# CPU2.net
KiCad netlist of a schematic drawn in Altium Designer
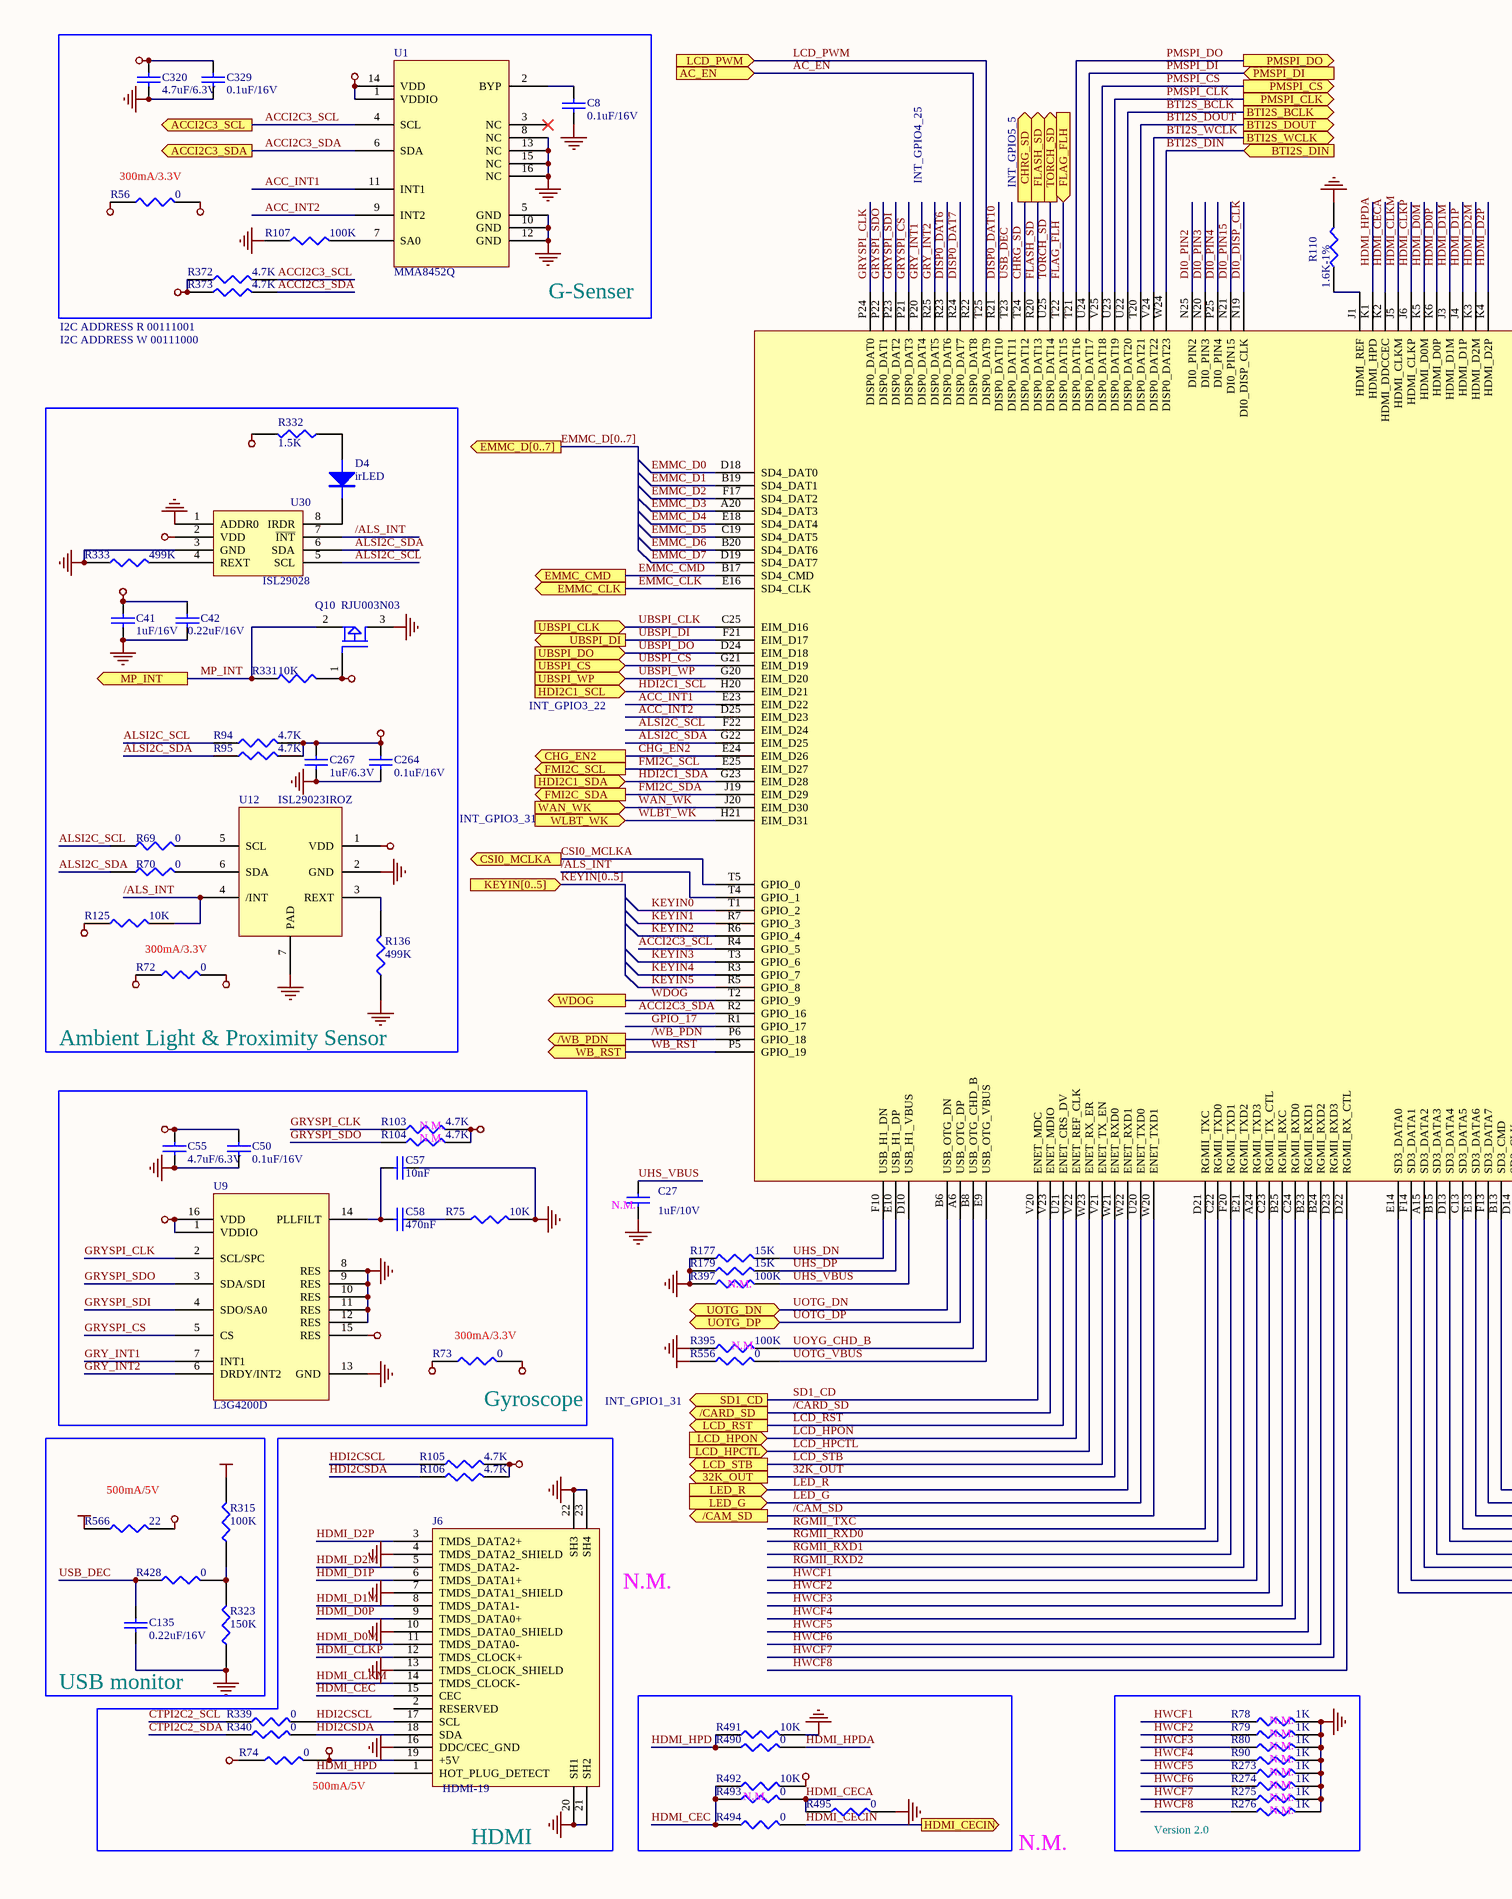
[diagram p0: CPU2.schdoc, left]
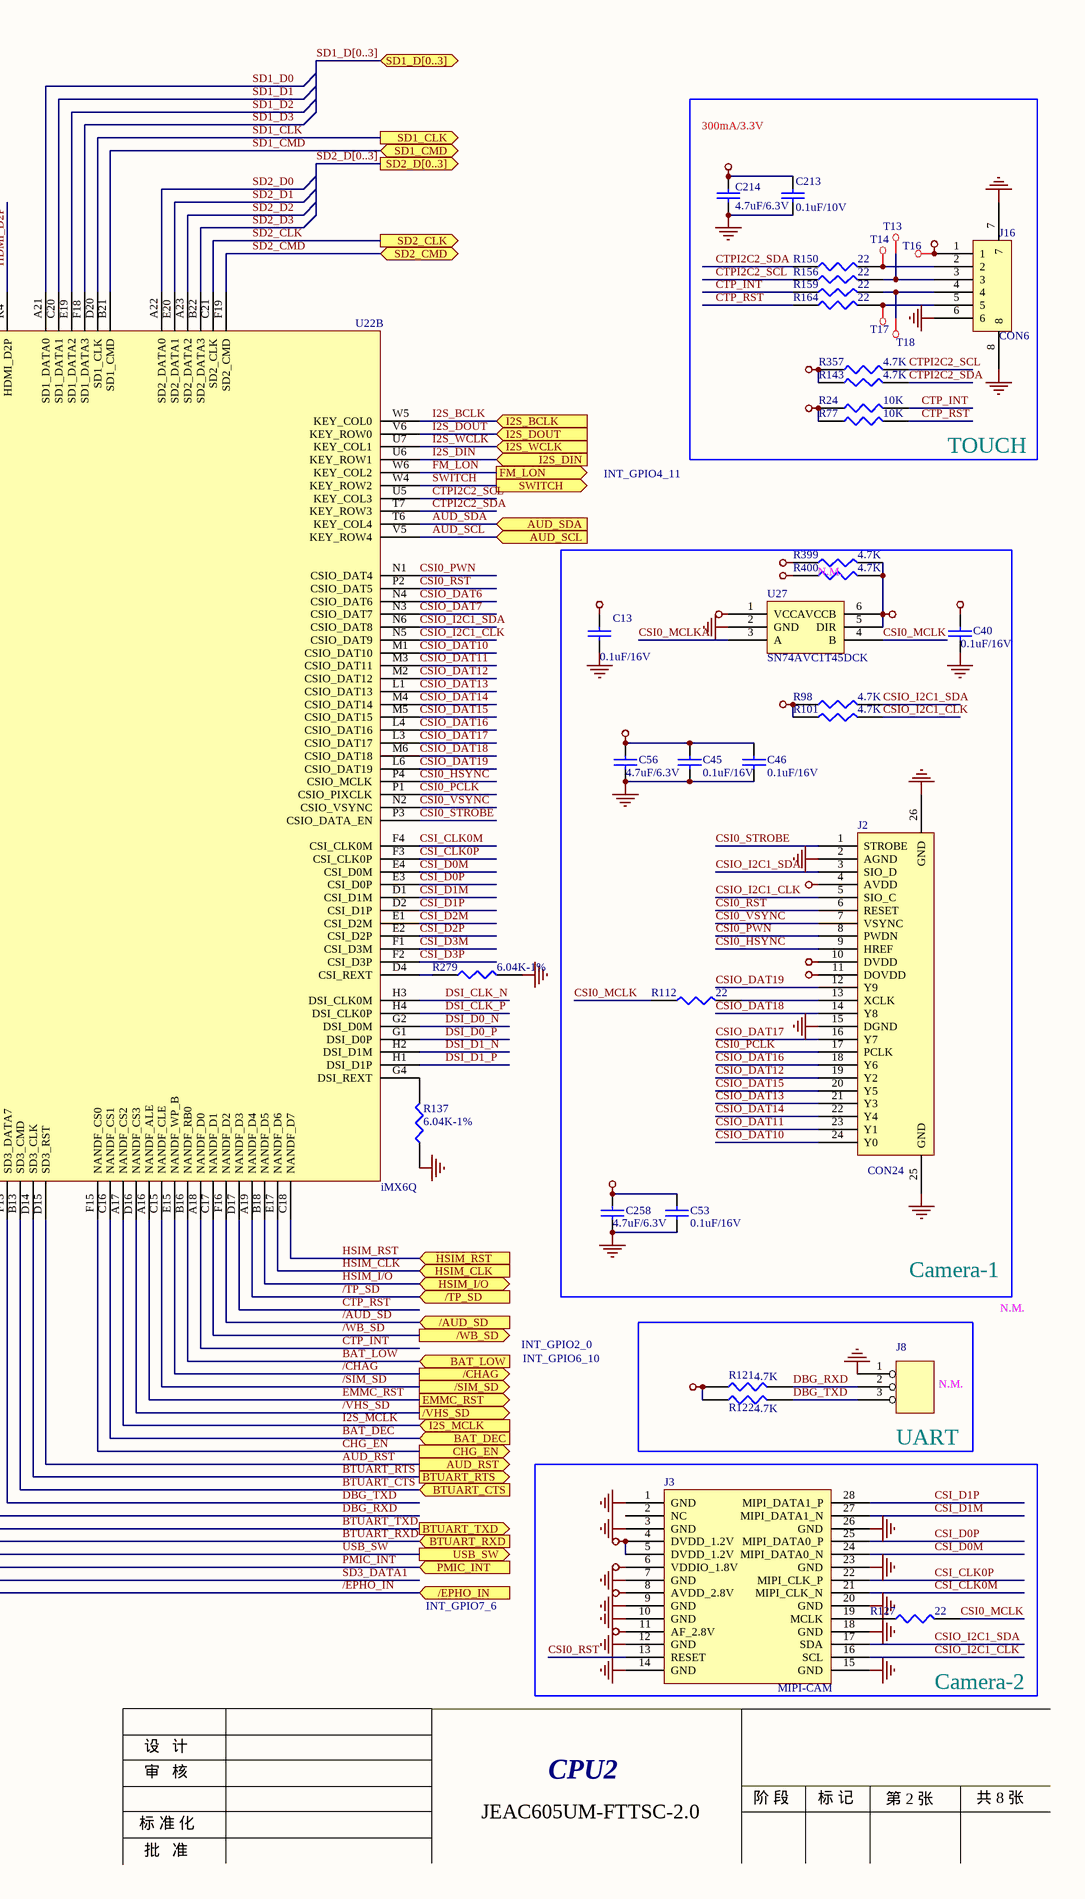
[diagram p1: CPU2.schdoc, right]

(export (version "E")
  (design (tool "Eeschema 10.0.6"))
  (components
    (comp (ref "C8") (value "0.1uF/16V") (footprint "C0402") (libsource (lib "*") (part "CAP")))
    (comp (ref "C13")
      (value "0.1uF/16V")
      (footprint "C0402")
      (description "Capacitor")
      (libsource (lib "*") (part "CAP"))
    )
    (comp (ref "C27")
      (value "1uF/10V")
      (footprint "C0603")
      (description "Capacitor")
      (libsource (lib "*") (part "CAP"))
    )
    (comp (ref "C40")
      (value "0.1uF/16V")
      (footprint "C0402")
      (description "Capacitor")
      (libsource (lib "*") (part "CAP"))
    )
    (comp (ref "C41")
      (value "1uF/16V")
      (footprint "C0402")
      (description "Capacitor")
      (libsource (lib "*") (part "CAP"))
    )
    (comp (ref "C42")
      (value "0.22uF/16V")
      (footprint "C0402")
      (description "Capacitor")
      (libsource (lib "*") (part "CAP"))
    )
    (comp (ref "C45")
      (value "0.1uF/16V")
      (footprint "C0402")
      (description "Capacitor")
      (libsource (lib "*") (part "CAP"))
    )
    (comp (ref "C46")
      (value "0.1uF/16V")
      (footprint "C0402")
      (description "Capacitor")
      (libsource (lib "*") (part "CAP"))
    )
    (comp (ref "C50") (value "0.1uF/16V") (footprint "C0402") (libsource (lib "*") (part "CAP")))
    (comp (ref "C53")
      (value "0.1uF/16V")
      (footprint "C0402")
      (description "Capacitor")
      (libsource (lib "*") (part "CAP"))
    )
    (comp (ref "C55") (value "4.7uF/6.3V") (footprint "C0603") (libsource (lib "*") (part "CAP")))
    (comp (ref "C56")
      (value "4.7uF/6.3V")
      (footprint "C0603")
      (description "Capacitor")
      (libsource (lib "*") (part "CAP"))
    )
    (comp (ref "C57") (value "10nF") (footprint "C0402") (libsource (lib "*") (part "CAP")))
    (comp (ref "C58") (value "470nF") (footprint "C0402") (libsource (lib "*") (part "CAP")))
    (comp (ref "C135")
      (value "0.22uF/16V")
      (footprint "C0402")
      (description "Capacitor")
      (libsource (lib "*") (part "CAP"))
    )
    (comp (ref "C213")
      (value "0.1uF/10V")
      (footprint "C0402")
      (description "Capacitor")
      (libsource (lib "*") (part "CAP"))
    )
    (comp (ref "C214")
      (value "4.7uF/6.3V")
      (footprint "C0603")
      (description "Capacitor")
      (libsource (lib "*") (part "CAP"))
    )
    (comp (ref "C258")
      (value "4.7uF/6.3V")
      (footprint "C0603")
      (description "Capacitor")
      (libsource (lib "*") (part "CAP"))
    )
    (comp (ref "C264") (value "0.1uF/16V") (footprint "C0402") (libsource (lib "*") (part "CAP")))
    (comp (ref "C267") (value "1uF/6.3V") (footprint "C0402") (libsource (lib "*") (part "CAP")))
    (comp (ref "C320") (value "4.7uF/6.3V") (footprint "C0603") (libsource (lib "*") (part "CAP")))
    (comp (ref "C329") (value "0.1uF/16V") (footprint "C0402") (libsource (lib "*") (part "CAP")))
    (comp (ref "D4") (value "irLED") (footprint "R0603") (libsource (lib "*") (part "DIODE")))
    (comp (ref "J2") (value "CON24") (footprint "J-CON-24-0_5") (libsource (lib "*") (part "CON-24")))
    (comp (ref "J3")
      (value "MIPI-CAM")
      (footprint "j-con-GB042-28P-H10-0_4")
      (libsource (lib "*") (part "MIPI-28"))
    )
    (comp (ref "J6") (value "HDMI-19") (footprint "j-con-19-0_4") (libsource (lib "*") (part "HDMI-19")))
    (comp (ref "J8") (value "~") (footprint "J-CON-3-2_1") (libsource (lib "*") (part "3 HEADER")))
    (comp (ref "J16") (value "CON6") (footprint "J-CON-6-0_5-ATOM") (libsource (lib "IMX53") (part "CON6")))
    (comp (ref "Q10") (value "RJU003N03") (footprint "SOT-23") (libsource (lib "*") (part "SI1021")))
    (comp (ref "R24") (value "10K") (footprint "R0402") (libsource (lib "*") (part "RES1")))
    (comp (ref "R56") (value "0") (footprint "R0402") (libsource (lib "*") (part "RES1")))
    (comp (ref "R69") (value "0") (footprint "R0402") (libsource (lib "*") (part "RES1")))
    (comp (ref "R70") (value "0") (footprint "R0402") (libsource (lib "*") (part "RES1")))
    (comp (ref "R72") (value "0") (footprint "R0402") (libsource (lib "*") (part "RES1")))
    (comp (ref "R73") (value "0") (footprint "R0402") (libsource (lib "*") (part "RES1")))
    (comp (ref "R74") (value "0") (footprint "R0603") (libsource (lib "*") (part "RES1")))
    (comp (ref "R75") (value "10K") (footprint "R0402") (libsource (lib "*") (part "RES1")))
    (comp (ref "R77") (value "10K") (footprint "R0402") (libsource (lib "*") (part "RES1")))
    (comp (ref "R78") (value "1K") (footprint "R0402") (libsource (lib "*") (part "RES1")))
    (comp (ref "R79") (value "1K") (footprint "R0402") (libsource (lib "*") (part "RES1")))
    (comp (ref "R80") (value "1K") (footprint "R0402") (libsource (lib "*") (part "RES1")))
    (comp (ref "R90") (value "1K") (footprint "R0402") (libsource (lib "*") (part "RES1")))
    (comp (ref "R94") (value "4.7K") (footprint "R0402") (libsource (lib "*") (part "RES1")))
    (comp (ref "R95") (value "4.7K") (footprint "R0402") (libsource (lib "*") (part "RES1")))
    (comp (ref "R98") (value "4.7K") (footprint "R0402") (libsource (lib "*") (part "RES1")))
    (comp (ref "R101") (value "4.7K") (footprint "R0402") (libsource (lib "*") (part "RES1")))
    (comp (ref "R103") (value "4.7K") (footprint "R0402") (libsource (lib "*") (part "RES1")))
    (comp (ref "R104") (value "4.7K") (footprint "R0402") (libsource (lib "*") (part "RES1")))
    (comp (ref "R105") (value "4.7K") (footprint "R0402") (libsource (lib "*") (part "RES1")))
    (comp (ref "R106") (value "4.7K") (footprint "R0402") (libsource (lib "*") (part "RES1")))
    (comp (ref "R107") (value "100K") (footprint "R0402") (libsource (lib "*") (part "RES1")))
    (comp (ref "R110") (value "1.6K-1%") (footprint "R0402") (libsource (lib "*") (part "RES1")))
    (comp (ref "R112") (value "22") (footprint "R0402") (libsource (lib "*") (part "RES1")))
    (comp (ref "R121") (value "4.7K") (footprint "R0402") (libsource (lib "*") (part "RES1")))
    (comp (ref "R122") (value "4.7K") (footprint "R0402") (libsource (lib "*") (part "RES1")))
    (comp (ref "R125") (value "10K") (footprint "R0402") (libsource (lib "*") (part "RES1")))
    (comp (ref "R127") (value "22") (footprint "R0402") (libsource (lib "*") (part "RES1")))
    (comp (ref "R136") (value "499K") (footprint "R0402") (libsource (lib "*") (part "RES1")))
    (comp (ref "R137") (value "6.04K-1%") (footprint "R0402") (libsource (lib "*") (part "RES1")))
    (comp (ref "R143") (value "4.7K") (footprint "R0402") (libsource (lib "*") (part "RES1")))
    (comp (ref "R150") (value "22") (footprint "R0402") (libsource (lib "*") (part "RES1")))
    (comp (ref "R156") (value "22") (footprint "R0402") (libsource (lib "*") (part "RES1")))
    (comp (ref "R159") (value "22") (footprint "R0402") (libsource (lib "*") (part "RES1")))
    (comp (ref "R164") (value "22") (footprint "R0402") (libsource (lib "*") (part "RES1")))
    (comp (ref "R177") (value "15K") (footprint "R0402") (libsource (lib "*") (part "RES1")))
    (comp (ref "R179") (value "15K") (footprint "R0402") (libsource (lib "*") (part "RES1")))
    (comp (ref "R273") (value "1K") (footprint "R0402") (libsource (lib "*") (part "RES1")))
    (comp (ref "R274") (value "1K") (footprint "R0402") (libsource (lib "*") (part "RES1")))
    (comp (ref "R275") (value "1K") (footprint "R0402") (libsource (lib "*") (part "RES1")))
    (comp (ref "R276") (value "1K") (footprint "R0402") (libsource (lib "*") (part "RES1")))
    (comp (ref "R279") (value "6.04K-1%") (footprint "R0402") (libsource (lib "*") (part "RES1")))
    (comp (ref "R315") (value "100K") (footprint "R0402") (libsource (lib "*") (part "RES1")))
    (comp (ref "R323") (value "150K") (footprint "R0402") (libsource (lib "*") (part "RES1")))
    (comp (ref "R331") (value "10K") (footprint "R0402") (libsource (lib "*") (part "RES1")))
    (comp (ref "R332") (value "1.5K") (footprint "R0402") (libsource (lib "*") (part "RES1")))
    (comp (ref "R333") (value "499K") (footprint "R0402") (libsource (lib "*") (part "RES1")))
    (comp (ref "R339") (value "0") (footprint "R0402") (libsource (lib "*") (part "RES1")))
    (comp (ref "R340") (value "0") (footprint "R0402") (libsource (lib "*") (part "RES1")))
    (comp (ref "R357") (value "4.7K") (footprint "R0402") (libsource (lib "*") (part "RES1")))
    (comp (ref "R372") (value "4.7K") (footprint "R0402") (libsource (lib "*") (part "RES1")))
    (comp (ref "R373") (value "4.7K") (footprint "R0402") (libsource (lib "*") (part "RES1")))
    (comp (ref "R395") (value "100K") (footprint "R0402") (libsource (lib "*") (part "RES1")))
    (comp (ref "R397") (value "100K") (footprint "R0402") (libsource (lib "*") (part "RES1")))
    (comp (ref "R399") (value "4.7K") (footprint "R0402") (libsource (lib "*") (part "RES1")))
    (comp (ref "R400") (value "4.7K") (footprint "R0402") (libsource (lib "*") (part "RES1")))
    (comp (ref "R428") (value "0") (footprint "R0402") (libsource (lib "*") (part "RES1")))
    (comp (ref "R490") (value "0") (footprint "R0402") (libsource (lib "*") (part "RES1")))
    (comp (ref "R491") (value "10K") (footprint "R0402") (libsource (lib "*") (part "RES1")))
    (comp (ref "R492") (value "10K") (footprint "R0402") (libsource (lib "*") (part "RES1")))
    (comp (ref "R493") (value "0") (footprint "R0402") (libsource (lib "*") (part "RES1")))
    (comp (ref "R494") (value "0") (footprint "R0402") (libsource (lib "*") (part "RES1")))
    (comp (ref "R495") (value "0") (footprint "R0402") (libsource (lib "*") (part "RES1")))
    (comp (ref "R556") (value "0") (footprint "R0402") (libsource (lib "*") (part "RES1")))
    (comp (ref "R566") (value "22") (footprint "R0402") (libsource (lib "*") (part "RES1")))
    (comp (ref "T13")
      (value "Testpoint")
      (footprint "TP2_0")
      (libsource (lib "DXP-SCHLIB") (part "Testpoint"))
    )
    (comp (ref "T14")
      (value "Testpoint")
      (footprint "TP2_0")
      (libsource (lib "DXP-SCHLIB") (part "Testpoint"))
    )
    (comp (ref "T16")
      (value "Testpoint")
      (footprint "TP2_0")
      (libsource (lib "DXP-SCHLIB") (part "Testpoint"))
    )
    (comp (ref "T17")
      (value "Testpoint")
      (footprint "TP2_0")
      (libsource (lib "DXP-SCHLIB") (part "Testpoint"))
    )
    (comp (ref "T18")
      (value "Testpoint")
      (footprint "TP2_0")
      (libsource (lib "DXP-SCHLIB") (part "Testpoint"))
    )
    (comp (ref "U1")
      (value "MMA8452Q")
      (footprint "U-DFN-16-0_5")
      (libsource (lib "IMX53") (part "MMA8452Q"))
    )
    (comp (ref "U9")
      (value "L3G4200D")
      (footprint "U-LGA-16-0_65")
      (libsource (lib "IMX53") (part "L3G4200D"))
    )
    (comp (ref "U12")
      (value "ISL29023IROZ")
      (footprint "U-ODFN-6-0_65")
      (libsource (lib "IMX53") (part "ISL29023IROZ"))
    )
    (comp (ref "U22") (value "iMX6Q") (footprint "U-BGA-624-0_8") (libsource (lib "Schlib1") (part "IMX6Q")))
    (comp (ref "U27")
      (value "SN74AVC1T45DCK")
      (footprint "SOT-363-6-0_65")
      (libsource (lib "TPS73701-SOT") (part "Component_1"))
    )
    (comp (ref "U30") (value "ISL29028") (footprint "U-ODFN-8-0_5") (libsource (lib "*") (part "ISL29028")))
  )
  (nets
    (net (code "1") (name "/32K_OUT") (class "Default")
      (node (ref "U22") (pin "W21") (pinfunction "ENET_RXD0_W21") (pintype "passive"))
    )
    (net (code "2") (name "/ACCI2C3_SCL") (class "Default")
      (node (ref "R372") (pin "2") (pinfunction "2_2") (pintype "passive"))
      (node (ref "U1") (pin "4") (pinfunction "SCL_4") (pintype "passive"))
      (node (ref "U22") (pin "R4") (pinfunction "GPIO_5_R4") (pintype "passive"))
    )
    (net (code "3") (name "/ACCI2C3_SDA") (class "Default")
      (node (ref "R373") (pin "2") (pinfunction "2_2") (pintype "passive"))
      (node (ref "U1") (pin "6") (pinfunction "SDA_6") (pintype "passive"))
      (node (ref "U22") (pin "R2") (pinfunction "GPIO_16_R2") (pintype "passive"))
    )
    (net (code "4") (name "/ACC_INT1") (class "Default")
      (node (ref "U1") (pin "11") (pinfunction "INT1_11") (pintype "passive"))
      (node (ref "U22") (pin "E23") (pinfunction "EIM_D22_E23") (pintype "passive"))
    )
    (net (code "5") (name "/ACC_INT2") (class "Default")
      (node (ref "U1") (pin "9") (pinfunction "INT2_9") (pintype "passive"))
      (node (ref "U22") (pin "D25") (pinfunction "EIM_D23_D25") (pintype "passive"))
    )
    (net (code "6") (name "/AC_EN") (class "Default")
      (node (ref "U22") (pin "R22") (pinfunction "DISP0_DAT8_R22") (pintype "passive"))
    )
    (net (code "7") (name "/ALSI2C_SCL") (class "Default")
      (node (ref "R69") (pin "1") (pinfunction "1_1") (pintype "passive"))
      (node (ref "R94") (pin "1") (pinfunction "1_1") (pintype "passive"))
      (node (ref "U22") (pin "F22") (pinfunction "EIM_D24_F22") (pintype "passive"))
      (node (ref "U30") (pin "5") (pinfunction "SCL_5") (pintype "passive"))
    )
    (net (code "8") (name "/ALSI2C_SDA") (class "Default")
      (node (ref "R70") (pin "1") (pinfunction "1_1") (pintype "passive"))
      (node (ref "R95") (pin "1") (pinfunction "1_1") (pintype "passive"))
      (node (ref "U22") (pin "G22") (pinfunction "EIM_D25_G22") (pintype "passive"))
      (node (ref "U30") (pin "6") (pinfunction "SDA_6") (pintype "passive"))
    )
    (net (code "9") (name "/AUD_RST") (class "Default")
      (node (ref "U22") (pin "D15") (pinfunction "SD3_RST_D15") (pintype "passive"))
    )
    (net (code "10") (name "/AUD_SCL") (class "Default")
      (node (ref "U22") (pin "V5") (pinfunction "KEY_ROW4_V5") (pintype "passive"))
    )
    (net (code "11") (name "/AUD_SDA") (class "Default")
      (node (ref "U22") (pin "T6") (pinfunction "KEY_COL4_T6") (pintype "passive"))
    )
    (net (code "12") (name "/BAT_DEC") (class "Default")
      (node (ref "U22") (pin "C16") (pinfunction "NANDF_CS1_C16") (pintype "passive"))
    )
    (net (code "13") (name "/BAT_LOW") (class "Default")
      (node (ref "U22") (pin "B16") (pinfunction "NANDF_RB0_B16") (pintype "passive"))
    )
    (net (code "14") (name "/BTI2S_BCLK") (class "Default")
      (node (ref "U22") (pin "U22") (pinfunction "DISP0_DAT20_U22") (pintype "passive"))
    )
    (net (code "15") (name "/BTI2S_DIN") (class "Default")
      (node (ref "U22") (pin "W24") (pinfunction "DISP0_DAT23_W24") (pintype "passive"))
    )
    (net (code "16") (name "/BTI2S_DOUT") (class "Default")
      (node (ref "U22") (pin "T20") (pinfunction "DISP0_DAT21_T20") (pintype "passive"))
    )
    (net (code "17") (name "/BTI2S_WCLK") (class "Default")
      (node (ref "U22") (pin "V24") (pinfunction "DISP0_DAT22_V24") (pintype "passive"))
    )
    (net (code "18") (name "/BTUART_CTS") (class "Default")
      (node (ref "U22") (pin "B13") (pinfunction "SD3_CMD_B13") (pintype "passive"))
    )
    (net (code "19") (name "/BTUART_RTS") (class "Default")
      (node (ref "U22") (pin "D14") (pinfunction "SD3_CLK_D14") (pintype "passive"))
    )
    (net (code "20") (name "/BTUART_RXD") (class "Default")
      (node (ref "U22") (pin "D13") (pinfunction "SD3_DATA4_D13") (pintype "passive"))
    )
    (net (code "21") (name "/BTUART_TXD") (class "Default")
      (node (ref "U22") (pin "C13") (pinfunction "SD3_DATA5_C13") (pintype "passive"))
    )
    (net (code "22") (name "/CHG_EN") (class "Default")
      (node (ref "U22") (pin "F15") (pinfunction "NANDF_CS0_F15") (pintype "passive"))
    )
    (net (code "23") (name "/CHG_EN2") (class "Default")
      (node (ref "U22") (pin "E24") (pinfunction "EIM_D26_E24") (pintype "passive"))
    )
    (net (code "24") (name "/CHRG_SD") (class "Default")
      (node (ref "U22") (pin "T24") (pinfunction "DISP0_DAT12_T24") (pintype "passive"))
    )
    (net (code "25") (name "/CSI0_HSYNC") (class "Default")
      (node (ref "J2") (pin "9") (pinfunction "HREF_9") (pintype "passive"))
      (node (ref "U22") (pin "P4") (pinfunction "CSIO_MCLK_P4") (pintype "passive"))
    )
    (net (code "26") (name "/CSI0_MCLK") (class "Default")
      (node (ref "R112") (pin "1") (pinfunction "1_1") (pintype "passive"))
      (node (ref "R127") (pin "2") (pinfunction "2_2") (pintype "passive"))
      (node (ref "U27") (pin "4") (pinfunction "B_4") (pintype "passive"))
    )
    (net (code "27") (name "/CSI0_MCLKA") (class "Default")
      (node (ref "U22") (pin "T5") (pinfunction "GPIO_0_T5") (pintype "passive"))
      (node (ref "U27") (pin "3") (pinfunction "A_3") (pintype "passive"))
    )
    (net (code "28") (name "/CSI0_PCLK") (class "Default")
      (node (ref "J2") (pin "17") (pinfunction "PCLK_17") (pintype "passive"))
      (node (ref "U22") (pin "P1") (pinfunction "CSIO_PIXCLK_P1") (pintype "passive"))
    )
    (net (code "29") (name "/CSI0_PWN") (class "Default")
      (node (ref "J2") (pin "8") (pinfunction "PWDN_8") (pintype "passive"))
      (node (ref "U22") (pin "N1") (pinfunction "CSIO_DAT4_N1") (pintype "passive"))
    )
    (net (code "30") (name "/CSI0_RST") (class "Default")
      (node (ref "J2") (pin "6") (pinfunction "RESET_6") (pintype "passive"))
      (node (ref "J3") (pin "13") (pinfunction "RESET_13") (pintype "passive"))
      (node (ref "U22") (pin "P2") (pinfunction "CSIO_DAT5_P2") (pintype "passive"))
    )
    (net (code "31") (name "/CSI0_STROBE") (class "Default")
      (node (ref "J2") (pin "1") (pinfunction "STROBE_1") (pintype "passive"))
      (node (ref "U22") (pin "P3") (pinfunction "CSIO_DATA_EN_P3") (pintype "passive"))
    )
    (net (code "32") (name "/CSI0_VSYNC") (class "Default")
      (node (ref "J2") (pin "7") (pinfunction "VSYNC_7") (pintype "passive"))
      (node (ref "U22") (pin "N2") (pinfunction "CSIO_VSYNC_N2") (pintype "passive"))
    )
    (net (code "33") (name "/CSIO_DAT6") (class "Default")
      (node (ref "U22") (pin "N4") (pinfunction "CSIO_DAT6_N4") (pintype "passive"))
    )
    (net (code "34") (name "/CSIO_DAT7") (class "Default")
      (node (ref "U22") (pin "N3") (pinfunction "CSIO_DAT7_N3") (pintype "passive"))
    )
    (net (code "35") (name "/CSIO_DAT10") (class "Default")
      (node (ref "J2") (pin "24") (pinfunction "Y0_24") (pintype "passive"))
      (node (ref "U22") (pin "M1") (pinfunction "CSIO_DAT10_M1") (pintype "passive"))
    )
    (net (code "36") (name "/CSIO_DAT11") (class "Default")
      (node (ref "J2") (pin "23") (pinfunction "Y1_23") (pintype "passive"))
      (node (ref "U22") (pin "M3") (pinfunction "CSIO_DAT11_M3") (pintype "passive"))
    )
    (net (code "37") (name "/CSIO_DAT12") (class "Default")
      (node (ref "J2") (pin "19") (pinfunction "Y2_19") (pintype "passive"))
      (node (ref "U22") (pin "M2") (pinfunction "CSIO_DAT12_M2") (pintype "passive"))
    )
    (net (code "38") (name "/CSIO_DAT13") (class "Default")
      (node (ref "J2") (pin "21") (pinfunction "Y3_21") (pintype "passive"))
      (node (ref "U22") (pin "L1") (pinfunction "CSIO_DAT13_L1") (pintype "passive"))
    )
    (net (code "39") (name "/CSIO_DAT14") (class "Default")
      (node (ref "J2") (pin "22") (pinfunction "Y4_22") (pintype "passive"))
      (node (ref "U22") (pin "M4") (pinfunction "CSIO_DAT14_M4") (pintype "passive"))
    )
    (net (code "40") (name "/CSIO_DAT15") (class "Default")
      (node (ref "J2") (pin "20") (pinfunction "Y5_20") (pintype "passive"))
      (node (ref "U22") (pin "M5") (pinfunction "CSIO_DAT15_M5") (pintype "passive"))
    )
    (net (code "41") (name "/CSIO_DAT16") (class "Default")
      (node (ref "J2") (pin "18") (pinfunction "Y6_18") (pintype "passive"))
      (node (ref "U22") (pin "L4") (pinfunction "CSIO_DAT16_L4") (pintype "passive"))
    )
    (net (code "42") (name "/CSIO_DAT17") (class "Default")
      (node (ref "J2") (pin "16") (pinfunction "Y7_16") (pintype "passive"))
      (node (ref "U22") (pin "L3") (pinfunction "CSIO_DAT17_L3") (pintype "passive"))
    )
    (net (code "43") (name "/CSIO_DAT18") (class "Default")
      (node (ref "J2") (pin "14") (pinfunction "Y8_14") (pintype "passive"))
      (node (ref "U22") (pin "M6") (pinfunction "CSIO_DAT18_M6") (pintype "passive"))
    )
    (net (code "44") (name "/CSIO_DAT19") (class "Default")
      (node (ref "J2") (pin "12") (pinfunction "Y9_12") (pintype "passive"))
      (node (ref "U22") (pin "L6") (pinfunction "CSIO_DAT19_L6") (pintype "passive"))
    )
    (net (code "45") (name "/CSIO_I2C1_CLK") (class "Default")
      (node (ref "J2") (pin "5") (pinfunction "SIO_C_5") (pintype "passive"))
      (node (ref "J3") (pin "16") (pinfunction "SCL_16") (pintype "passive"))
      (node (ref "R101") (pin "2") (pinfunction "2_2") (pintype "passive"))
      (node (ref "U22") (pin "N5") (pinfunction "CSIO_DAT9_N5") (pintype "passive"))
    )
    (net (code "46") (name "/CSIO_I2C1_SDA") (class "Default")
      (node (ref "J2") (pin "3") (pinfunction "SIO_D_3") (pintype "passive"))
      (node (ref "J3") (pin "17") (pinfunction "SDA_17") (pintype "passive"))
      (node (ref "R98") (pin "2") (pinfunction "2_2") (pintype "passive"))
      (node (ref "U22") (pin "N6") (pinfunction "CSIO_DAT8_N6") (pintype "passive"))
    )
    (net (code "47") (name "/CSI_CLK0M") (class "Default")
      (node (ref "J3") (pin "21") (pinfunction "MIPI_CLK_N_21") (pintype "passive"))
      (node (ref "U22") (pin "F4") (pinfunction "CSI_CLK0M_F4") (pintype "passive"))
    )
    (net (code "48") (name "/CSI_CLK0P") (class "Default")
      (node (ref "J3") (pin "22") (pinfunction "MIPI_CLK_P_22") (pintype "passive"))
      (node (ref "U22") (pin "F3") (pinfunction "CSI_CLK0P_F3") (pintype "passive"))
    )
    (net (code "49") (name "/CSI_D0M") (class "Default")
      (node (ref "J3") (pin "24") (pinfunction "MIPI_DATA0_N_24") (pintype "passive"))
      (node (ref "U22") (pin "E4") (pinfunction "CSI_D0M_E4") (pintype "passive"))
    )
    (net (code "50") (name "/CSI_D0P") (class "Default")
      (node (ref "J3") (pin "25") (pinfunction "MIPI_DATA0_P_25") (pintype "passive"))
      (node (ref "U22") (pin "E3") (pinfunction "CSI_D0P_E3") (pintype "passive"))
    )
    (net (code "51") (name "/CSI_D1M") (class "Default")
      (node (ref "J3") (pin "27") (pinfunction "MIPI_DATA1_N_27") (pintype "passive"))
      (node (ref "U22") (pin "D1") (pinfunction "CSI_D1M_D1") (pintype "passive"))
    )
    (net (code "52") (name "/CSI_D1P") (class "Default")
      (node (ref "J3") (pin "28") (pinfunction "MIPI_DATA1_P_28") (pintype "passive"))
      (node (ref "U22") (pin "D2") (pinfunction "CSI_D1P_D2") (pintype "passive"))
    )
    (net (code "53") (name "/CSI_D2M") (class "Default")
      (node (ref "U22") (pin "E1") (pinfunction "CSI_D2M_E1") (pintype "passive"))
    )
    (net (code "54") (name "/CSI_D2P") (class "Default")
      (node (ref "U22") (pin "E2") (pinfunction "CSI_D2P_E2") (pintype "passive"))
    )
    (net (code "55") (name "/CSI_D3M") (class "Default")
      (node (ref "U22") (pin "F1") (pinfunction "CSI_D3M_F1") (pintype "passive"))
    )
    (net (code "56") (name "/CSI_D3P") (class "Default")
      (node (ref "U22") (pin "F2") (pinfunction "CSI_D3P_F2") (pintype "passive"))
    )
    (net (code "57") (name "/CTPI2C2_SCL") (class "Default")
      (node (ref "R156") (pin "1") (pinfunction "1_1") (pintype "passive"))
      (node (ref "R339") (pin "1") (pinfunction "1_1") (pintype "passive"))
      (node (ref "R357") (pin "2") (pinfunction "2_2") (pintype "passive"))
      (node (ref "U22") (pin "U5") (pinfunction "KEY_COL3_U5") (pintype "passive"))
    )
    (net (code "58") (name "/CTPI2C2_SDA") (class "Default")
      (node (ref "R143") (pin "2") (pinfunction "2_2") (pintype "passive"))
      (node (ref "R150") (pin "1") (pinfunction "1_1") (pintype "passive"))
      (node (ref "R340") (pin "1") (pinfunction "1_1") (pintype "passive"))
      (node (ref "U22") (pin "T7") (pinfunction "KEY_ROW3_T7") (pintype "passive"))
    )
    (net (code "59") (name "/CTP_INT") (class "Default")
      (node (ref "R159") (pin "1") (pinfunction "1_1") (pintype "passive"))
      (node (ref "R24") (pin "2") (pinfunction "2_2") (pintype "passive"))
      (node (ref "U22") (pin "A18") (pinfunction "NANDF_D0_A18") (pintype "passive"))
    )
    (net (code "60") (name "/CTP_RST") (class "Default")
      (node (ref "R164") (pin "1") (pinfunction "1_1") (pintype "passive"))
      (node (ref "R77") (pin "2") (pinfunction "2_2") (pintype "passive"))
      (node (ref "U22") (pin "D17") (pinfunction "NANDF_D3_D17") (pintype "passive"))
    )
    (net (code "61") (name "/DBG_RXD") (class "Default")
      (node (ref "J8") (pin "2") (pintype "passive"))
      (node (ref "R121") (pin "2") (pinfunction "2_2") (pintype "passive"))
      (node (ref "U22") (pin "E13") (pinfunction "SD3_DATA6_E13") (pintype "passive"))
    )
    (net (code "62") (name "/DBG_TXD") (class "Default")
      (node (ref "J8") (pin "3") (pintype "passive"))
      (node (ref "R122") (pin "2") (pinfunction "2_2") (pintype "passive"))
      (node (ref "U22") (pin "F13") (pinfunction "SD3_DATA7_F13") (pintype "passive"))
    )
    (net (code "63") (name "/DI0_DISP_CLK") (class "Default")
      (node (ref "U22") (pin "N19") (pinfunction "DI0_DISP_CLK_N19") (pintype "passive"))
    )
    (net (code "64") (name "/DI0_PIN2") (class "Default")
      (node (ref "U22") (pin "N25") (pinfunction "DI0_PIN2_N25") (pintype "passive"))
    )
    (net (code "65") (name "/DI0_PIN3") (class "Default")
      (node (ref "U22") (pin "N20") (pinfunction "DI0_PIN3_N20") (pintype "passive"))
    )
    (net (code "66") (name "/DI0_PIN4") (class "Default")
      (node (ref "U22") (pin "P25") (pinfunction "DI0_PIN4_P25") (pintype "passive"))
    )
    (net (code "67") (name "/DI0_PIN15") (class "Default")
      (node (ref "U22") (pin "N21") (pinfunction "DI0_PIN15_N21") (pintype "passive"))
    )
    (net (code "68") (name "/DISP0_DAT6") (class "Default")
      (node (ref "U22") (pin "R23") (pinfunction "DISP0_DAT6_R23") (pintype "passive"))
    )
    (net (code "69") (name "/DISP0_DAT7") (class "Default")
      (node (ref "U22") (pin "R24") (pinfunction "DISP0_DAT7_R24") (pintype "passive"))
    )
    (net (code "70") (name "/DISP0_DAT10") (class "Default")
      (node (ref "U22") (pin "R21") (pinfunction "DISP0_DAT10_R21") (pintype "passive"))
    )
    (net (code "71") (name "/DSI_CLK_N") (class "Default")
      (node (ref "U22") (pin "H3") (pinfunction "DSI_CLK0M_H3") (pintype "passive"))
    )
    (net (code "72") (name "/DSI_CLK_P") (class "Default")
      (node (ref "U22") (pin "H4") (pinfunction "DSI_CLK0P_H4") (pintype "passive"))
    )
    (net (code "73") (name "/DSI_D0_N") (class "Default")
      (node (ref "U22") (pin "G2") (pinfunction "DSI_D0M_G2") (pintype "passive"))
    )
    (net (code "74") (name "/DSI_D0_P") (class "Default")
      (node (ref "U22") (pin "G1") (pinfunction "DSI_D0P_G1") (pintype "passive"))
    )
    (net (code "75") (name "/DSI_D1_N") (class "Default")
      (node (ref "U22") (pin "H2") (pinfunction "DSI_D1M_H2") (pintype "passive"))
    )
    (net (code "76") (name "/DSI_D1_P") (class "Default")
      (node (ref "U22") (pin "H1") (pinfunction "DSI_D1P_H1") (pintype "passive"))
    )
    (net (code "77") (name "/EMMC_CLK") (class "Default")
      (node (ref "U22") (pin "E16") (pinfunction "SD4_CLK_E16") (pintype "passive"))
    )
    (net (code "78") (name "/EMMC_CMD") (class "Default")
      (node (ref "U22") (pin "B17") (pinfunction "SD4_CMD_B17") (pintype "passive"))
    )
    (net (code "79") (name "/EMMC_D0") (class "Default")
      (node (ref "U22") (pin "D18") (pinfunction "SD4_DAT0_D18") (pintype "passive"))
    )
    (net (code "80") (name "/EMMC_D1") (class "Default")
      (node (ref "U22") (pin "B19") (pinfunction "SD4_DAT1_B19") (pintype "passive"))
    )
    (net (code "81") (name "/EMMC_D2") (class "Default")
      (node (ref "U22") (pin "F17") (pinfunction "SD4_DAT2_F17") (pintype "passive"))
    )
    (net (code "82") (name "/EMMC_D3") (class "Default")
      (node (ref "U22") (pin "A20") (pinfunction "SD4_DAT3_A20") (pintype "passive"))
    )
    (net (code "83") (name "/EMMC_D4") (class "Default")
      (node (ref "U22") (pin "E18") (pinfunction "SD4_DAT4_E18") (pintype "passive"))
    )
    (net (code "84") (name "/EMMC_D5") (class "Default")
      (node (ref "U22") (pin "C19") (pinfunction "SD4_DAT5_C19") (pintype "passive"))
    )
    (net (code "85") (name "/EMMC_D6") (class "Default")
      (node (ref "U22") (pin "B20") (pinfunction "SD4_DAT6_B20") (pintype "passive"))
    )
    (net (code "86") (name "/EMMC_D7") (class "Default")
      (node (ref "U22") (pin "D19") (pinfunction "SD4_DAT7_D19") (pintype "passive"))
    )
    (net (code "88") (name "/EMMC_RST") (class "Default")
      (node (ref "U22") (pin "A16") (pinfunction "NANDF_ALE_A16") (pintype "passive"))
    )
    (net (code "89") (name "/FLAG_FLH") (class "Default")
      (node (ref "U22") (pin "T22") (pinfunction "DISP0_DAT15_T22") (pintype "passive"))
    )
    (net (code "90") (name "/FLASH_SD") (class "Default")
      (node (ref "U22") (pin "R20") (pinfunction "DISP0_DAT13_R20") (pintype "passive"))
    )
    (net (code "91") (name "/FMI2C_SCL") (class "Default")
      (node (ref "U22") (pin "E25") (pinfunction "EIM_D27_E25") (pintype "passive"))
    )
    (net (code "92") (name "/FMI2C_SDA") (class "Default")
      (node (ref "U22") (pin "J19") (pinfunction "EIM_D29_J19") (pintype "passive"))
    )
    (net (code "93") (name "/FM_LON") (class "Default")
      (node (ref "U22") (pin "W6") (pinfunction "KEY_COL2_W6") (pintype "passive"))
    )
    (net (code "94") (name "/GPIO_17") (class "Default")
      (node (ref "U22") (pin "R1") (pinfunction "GPIO_17_R1") (pintype "passive"))
    )
    (net (code "95") (name "/GRYSPI_CLK") (class "Default")
      (node (ref "R103") (pin "1") (pinfunction "1_1") (pintype "passive"))
      (node (ref "U22") (pin "P24") (pinfunction "DISP0_DAT0_P24") (pintype "passive"))
      (node (ref "U9") (pin "2") (pinfunction "SCL/SPC_2") (pintype "passive"))
    )
    (net (code "96") (name "/GRYSPI_CS") (class "Default")
      (node (ref "U22") (pin "P21") (pinfunction "DISP0_DAT3_P21") (pintype "passive"))
      (node (ref "U9") (pin "5") (pinfunction "CS_5") (pintype "passive"))
    )
    (net (code "97") (name "/GRYSPI_SDI") (class "Default")
      (node (ref "U22") (pin "P23") (pinfunction "DISP0_DAT2_P23") (pintype "passive"))
      (node (ref "U9") (pin "4") (pinfunction "SDO/SA0_4") (pintype "passive"))
    )
    (net (code "98") (name "/GRYSPI_SDO") (class "Default")
      (node (ref "R104") (pin "1") (pinfunction "1_1") (pintype "passive"))
      (node (ref "U22") (pin "P22") (pinfunction "DISP0_DAT1_P22") (pintype "passive"))
      (node (ref "U9") (pin "3") (pinfunction "SDA/SDI_3") (pintype "passive"))
    )
    (net (code "99") (name "/GRY_INT1") (class "Default")
      (node (ref "U22") (pin "P20") (pinfunction "DISP0_DAT4_P20") (pintype "passive"))
      (node (ref "U9") (pin "7") (pinfunction "INT1_7") (pintype "passive"))
    )
    (net (code "100") (name "/GRY_INT2") (class "Default")
      (node (ref "U22") (pin "R25") (pinfunction "DISP0_DAT5_R25") (pintype "passive"))
      (node (ref "U9") (pin "6") (pinfunction "DRDY/INT2_6") (pintype "passive"))
    )
    (net (code "101") (name "/HDI2C1_SCL") (class "Default")
      (node (ref "U22") (pin "H20") (pinfunction "EIM_D21_H20") (pintype "passive"))
    )
    (net (code "102") (name "/HDI2C1_SDA") (class "Default")
      (node (ref "U22") (pin "G23") (pinfunction "EIM_D28_G23") (pintype "passive"))
    )
    (net (code "103") (name "/HDI2CSCL") (class "Default")
      (node (ref "J6") (pin "17") (pinfunction "SCL_17") (pintype "passive"))
      (node (ref "R105") (pin "1") (pinfunction "1_1") (pintype "passive"))
      (node (ref "R339") (pin "2") (pinfunction "2_2") (pintype "passive"))
    )
    (net (code "104") (name "/HDI2CSDA") (class "Default")
      (node (ref "J6") (pin "18") (pinfunction "SDA_18") (pintype "passive"))
      (node (ref "R106") (pin "1") (pinfunction "1_1") (pintype "passive"))
      (node (ref "R340") (pin "2") (pinfunction "2_2") (pintype "passive"))
    )
    (net (code "105") (name "/HDMI_CEC") (class "Default")
      (node (ref "J6") (pin "15") (pinfunction "CEC_15") (pintype "passive"))
      (node (ref "R492") (pin "1") (pinfunction "1_1") (pintype "passive"))
      (node (ref "R493") (pin "1") (pinfunction "1_1") (pintype "passive"))
      (node (ref "R494") (pin "1") (pinfunction "1_1") (pintype "passive"))
    )
    (net (code "106") (name "/HDMI_CECA") (class "Default")
      (node (ref "R493") (pin "2") (pinfunction "2_2") (pintype "passive"))
      (node (ref "R495") (pin "1") (pinfunction "1_1") (pintype "passive"))
      (node (ref "U22") (pin "K2") (pinfunction "HDMI_DDCCEC_K2") (pintype "passive"))
    )
    (net (code "107") (name "/HDMI_CECIN") (class "Default")
      (node (ref "R494") (pin "2") (pinfunction "2_2") (pintype "passive"))
    )
    (net (code "108") (name "/HDMI_CLKM") (class "Default")
      (node (ref "J6") (pin "14") (pinfunction "TMDS_CLOCK-_14") (pintype "passive"))
      (node (ref "U22") (pin "J5") (pinfunction "HDMI_CLKM_J5") (pintype "passive"))
    )
    (net (code "109") (name "/HDMI_CLKP") (class "Default")
      (node (ref "J6") (pin "12") (pinfunction "TMDS_CLOCK+_12") (pintype "passive"))
      (node (ref "U22") (pin "J6") (pinfunction "HDMI_CLKP_J6") (pintype "passive"))
    )
    (net (code "110") (name "/HDMI_D0M") (class "Default")
      (node (ref "J6") (pin "11") (pinfunction "TMDS_DATA0-_11") (pintype "passive"))
      (node (ref "U22") (pin "K5") (pinfunction "HDMI_D0M_K5") (pintype "passive"))
    )
    (net (code "111") (name "/HDMI_D0P") (class "Default")
      (node (ref "J6") (pin "9") (pinfunction "TMDS_DATA0+_9") (pintype "passive"))
      (node (ref "U22") (pin "K6") (pinfunction "HDMI_D0P_K6") (pintype "passive"))
    )
    (net (code "112") (name "/HDMI_D1M") (class "Default")
      (node (ref "J6") (pin "8") (pinfunction "TMDS_DATA1-_8") (pintype "passive"))
      (node (ref "U22") (pin "J3") (pinfunction "HDMI_D1M_J3") (pintype "passive"))
    )
    (net (code "113") (name "/HDMI_D1P") (class "Default")
      (node (ref "J6") (pin "6") (pinfunction "TMDS_DATA1+_6") (pintype "passive"))
      (node (ref "U22") (pin "J4") (pinfunction "HDMI_D1P_J4") (pintype "passive"))
    )
    (net (code "114") (name "/HDMI_D2M") (class "Default")
      (node (ref "J6") (pin "5") (pinfunction "TMDS_DATA2-_5") (pintype "passive"))
      (node (ref "U22") (pin "K3") (pinfunction "HDMI_D2M_K3") (pintype "passive"))
    )
    (net (code "115") (name "/HDMI_D2P") (class "Default")
      (node (ref "J6") (pin "3") (pinfunction "TMDS_DATA2+_3") (pintype "passive"))
      (node (ref "U22") (pin "K4") (pinfunction "HDMI_D2P_K4") (pintype "passive"))
    )
    (net (code "116") (name "/HDMI_HPD") (class "Default")
      (node (ref "J6") (pin "1") (pinfunction "HOT_PLUG_DETECT_1") (pintype "passive"))
      (node (ref "R490") (pin "1") (pinfunction "1_1") (pintype "passive"))
      (node (ref "R491") (pin "1") (pinfunction "1_1") (pintype "passive"))
    )
    (net (code "117") (name "/HDMI_HPDA") (class "Default")
      (node (ref "R490") (pin "2") (pinfunction "2_2") (pintype "passive"))
      (node (ref "U22") (pin "K1") (pinfunction "HDMI_HPD_K1") (pintype "passive"))
    )
    (net (code "118") (name "/HSIM_CLK") (class "Default")
      (node (ref "U22") (pin "E17") (pinfunction "NANDF_D6_E17") (pintype "passive"))
    )
    (net (code "119") (name "/HSIM_I{slash}O") (class "Default")
      (node (ref "U22") (pin "B18") (pinfunction "NANDF_D5_B18") (pintype "passive"))
    )
    (net (code "120") (name "/HSIM_RST") (class "Default")
      (node (ref "U22") (pin "C18") (pinfunction "NANDF_D7_C18") (pintype "passive"))
    )
    (net (code "121") (name "/HWCF1") (class "Default")
      (node (ref "R78") (pin "1") (pinfunction "1_1") (pintype "passive"))
      (node (ref "U22") (pin "A24") (pinfunction "RGMII_TXD3_A24") (pintype "passive"))
    )
    (net (code "122") (name "/HWCF2") (class "Default")
      (node (ref "R79") (pin "1") (pinfunction "1_1") (pintype "passive"))
      (node (ref "U22") (pin "C23") (pinfunction "RGMII_TX_CTL_C23") (pintype "passive"))
    )
    (net (code "123") (name "/HWCF3") (class "Default")
      (node (ref "R80") (pin "1") (pinfunction "1_1") (pintype "passive"))
      (node (ref "U22") (pin "B25") (pinfunction "RGMII_RXC_B25") (pintype "passive"))
    )
    (net (code "124") (name "/HWCF4") (class "Default")
      (node (ref "R90") (pin "1") (pinfunction "1_1") (pintype "passive"))
      (node (ref "U22") (pin "C24") (pinfunction "RGMII_RXD0_C24") (pintype "passive"))
    )
    (net (code "125") (name "/HWCF5") (class "Default")
      (node (ref "R273") (pin "1") (pinfunction "1_1") (pintype "passive"))
      (node (ref "U22") (pin "B23") (pinfunction "RGMII_RXD1_B23") (pintype "passive"))
    )
    (net (code "126") (name "/HWCF6") (class "Default")
      (node (ref "R274") (pin "1") (pinfunction "1_1") (pintype "passive"))
      (node (ref "U22") (pin "B24") (pinfunction "RGMII_RXD2_B24") (pintype "passive"))
    )
    (net (code "127") (name "/HWCF7") (class "Default")
      (node (ref "R275") (pin "1") (pinfunction "1_1") (pintype "passive"))
      (node (ref "U22") (pin "D23") (pinfunction "RGMII_RXD3_D23") (pintype "passive"))
    )
    (net (code "128") (name "/HWCF8") (class "Default")
      (node (ref "R276") (pin "1") (pinfunction "1_1") (pintype "passive"))
      (node (ref "U22") (pin "D22") (pinfunction "RGMII_RX_CTL_D22") (pintype "passive"))
    )
    (net (code "129") (name "/I2S_BCLK") (class "Default")
      (node (ref "U22") (pin "W5") (pinfunction "KEY_COL0_W5") (pintype "passive"))
    )
    (net (code "130") (name "/I2S_DIN") (class "Default")
      (node (ref "U22") (pin "U6") (pinfunction "KEY_ROW1_U6") (pintype "passive"))
    )
    (net (code "131") (name "/I2S_DOUT") (class "Default")
      (node (ref "U22") (pin "V6") (pinfunction "KEY_ROW0_V6") (pintype "passive"))
    )
    (net (code "132") (name "/I2S_MCLK") (class "Default")
      (node (ref "U22") (pin "A17") (pinfunction "NANDF_CS2_A17") (pintype "passive"))
    )
    (net (code "133") (name "/I2S_WCLK") (class "Default")
      (node (ref "U22") (pin "U7") (pinfunction "KEY_COL1_U7") (pintype "passive"))
    )
    (net (code "134") (name "/KEYIN0") (class "Default")
      (node (ref "U22") (pin "T1") (pinfunction "GPIO_2_T1") (pintype "passive"))
    )
    (net (code "135") (name "/KEYIN1") (class "Default")
      (node (ref "U22") (pin "R7") (pinfunction "GPIO_3_R7") (pintype "passive"))
    )
    (net (code "136") (name "/KEYIN2") (class "Default")
      (node (ref "U22") (pin "R6") (pinfunction "GPIO_4_R6") (pintype "passive"))
    )
    (net (code "137") (name "/KEYIN3") (class "Default")
      (node (ref "U22") (pin "T3") (pinfunction "GPIO_6_T3") (pintype "passive"))
    )
    (net (code "138") (name "/KEYIN4") (class "Default")
      (node (ref "U22") (pin "R3") (pinfunction "GPIO_7_R3") (pintype "passive"))
    )
    (net (code "139") (name "/KEYIN5") (class "Default")
      (node (ref "U22") (pin "R5") (pinfunction "GPIO_8_R5") (pintype "passive"))
    )
    (net (code "141") (name "/LCD_HPCTL") (class "Default")
      (node (ref "U22") (pin "W23") (pinfunction "ENET_RX_ER_W23") (pintype "passive"))
    )
    (net (code "142") (name "/LCD_HPON") (class "Default")
      (node (ref "U22") (pin "V22") (pinfunction "ENET_REF_CLK_V22") (pintype "passive"))
    )
    (net (code "143") (name "/LCD_PWM") (class "Default")
      (node (ref "U22") (pin "T25") (pinfunction "DISP0_DAT9_T25") (pintype "passive"))
    )
    (net (code "144") (name "/LCD_RST") (class "Default")
      (node (ref "U22") (pin "U21") (pinfunction "ENET_CRS_DV_U21") (pintype "passive"))
    )
    (net (code "145") (name "/LCD_STB") (class "Default")
      (node (ref "U22") (pin "V21") (pinfunction "ENET_TX_EN_V21") (pintype "passive"))
    )
    (net (code "146") (name "/LED_G") (class "Default")
      (node (ref "U22") (pin "U20") (pinfunction "ENET_TXD0_U20") (pintype "passive"))
    )
    (net (code "147") (name "/LED_R") (class "Default")
      (node (ref "U22") (pin "W22") (pinfunction "ENET_RXD1_W22") (pintype "passive"))
    )
    (net (code "148") (name "/MP_INT") (class "Default")
      (node (ref "Q10") (pin "2") (pinfunction "S_2") (pintype "passive"))
      (node (ref "R331") (pin "1") (pinfunction "1_1") (pintype "passive"))
    )
    (net (code "149") (name "/PMIC_INT") (class "Default")
      (node (ref "U22") (pin "A15") (pinfunction "SD3_DATA2_A15") (pintype "passive"))
    )
    (net (code "150") (name "/PMSPI_CLK") (class "Default")
      (node (ref "U22") (pin "U23") (pinfunction "DISP0_DAT19_U23") (pintype "passive"))
    )
    (net (code "151") (name "/PMSPI_CS") (class "Default")
      (node (ref "U22") (pin "V25") (pinfunction "DISP0_DAT18_V25") (pintype "passive"))
    )
    (net (code "152") (name "/PMSPI_DI") (class "Default")
      (node (ref "U22") (pin "U24") (pinfunction "DISP0_DAT17_U24") (pintype "passive"))
    )
    (net (code "153") (name "/PMSPI_DO") (class "Default")
      (node (ref "U22") (pin "T21") (pinfunction "DISP0_DAT16_T21") (pintype "passive"))
    )
    (net (code "154") (name "/RGMII_RXD0") (class "Default")
      (node (ref "U22") (pin "C22") (pinfunction "RGMII_TXD0_C22") (pintype "passive"))
    )
    (net (code "155") (name "/RGMII_RXD1") (class "Default")
      (node (ref "U22") (pin "F20") (pinfunction "RGMII_TXD1_F20") (pintype "passive"))
    )
    (net (code "156") (name "/RGMII_RXD2") (class "Default")
      (node (ref "U22") (pin "E21") (pinfunction "RGMII_TXD2_E21") (pintype "passive"))
    )
    (net (code "157") (name "/RGMII_TXC") (class "Default")
      (node (ref "U22") (pin "D21") (pinfunction "RGMII_TXC_D21") (pintype "passive"))
    )
    (net (code "158") (name "/SD1_CD") (class "Default")
      (node (ref "U22") (pin "V20") (pinfunction "ENET_MDC_V20") (pintype "passive"))
    )
    (net (code "159") (name "/SD1_CLK") (class "Default")
      (node (ref "U22") (pin "D20") (pinfunction "SD1_CLK_D20") (pintype "passive"))
    )
    (net (code "160") (name "/SD1_CMD") (class "Default")
      (node (ref "U22") (pin "B21") (pinfunction "SD1_CMD_B21") (pintype "passive"))
    )
    (net (code "161") (name "/SD1_D0") (class "Default")
      (node (ref "U22") (pin "A21") (pinfunction "SD1_DATA0_A21") (pintype "passive"))
    )
    (net (code "162") (name "/SD1_D1") (class "Default")
      (node (ref "U22") (pin "C20") (pinfunction "SD1_DATA1_C20") (pintype "passive"))
    )
    (net (code "163") (name "/SD1_D2") (class "Default")
      (node (ref "U22") (pin "E19") (pinfunction "SD1_DATA2_E19") (pintype "passive"))
    )
    (net (code "164") (name "/SD1_D3") (class "Default")
      (node (ref "U22") (pin "F18") (pinfunction "SD1_DATA3_F18") (pintype "passive"))
    )
    (net (code "166") (name "/SD2_CLK") (class "Default")
      (node (ref "U22") (pin "C21") (pinfunction "SD2_CLK_C21") (pintype "passive"))
    )
    (net (code "167") (name "/SD2_CMD") (class "Default")
      (node (ref "U22") (pin "F19") (pinfunction "SD2_CMD_F19") (pintype "passive"))
    )
    (net (code "168") (name "/SD2_D0") (class "Default")
      (node (ref "U22") (pin "A22") (pinfunction "SD2_DATA0_A22") (pintype "passive"))
    )
    (net (code "169") (name "/SD2_D1") (class "Default")
      (node (ref "U22") (pin "E20") (pinfunction "SD2_DATA1_E20") (pintype "passive"))
    )
    (net (code "170") (name "/SD2_D2") (class "Default")
      (node (ref "U22") (pin "A23") (pinfunction "SD2_DATA2_A23") (pintype "passive"))
    )
    (net (code "171") (name "/SD2_D3") (class "Default")
      (node (ref "U22") (pin "B22") (pinfunction "SD2_DATA3_B22") (pintype "passive"))
    )
    (net (code "173") (name "/SD3_DATA1") (class "Default")
      (node (ref "U22") (pin "F14") (pinfunction "SD3_DATA1_F14") (pintype "passive"))
    )
    (net (code "174") (name "/SWITCH") (class "Default")
      (node (ref "U22") (pin "W4") (pinfunction "KEY_ROW2_W4") (pintype "passive"))
    )
    (net (code "175") (name "/TORCH_SD") (class "Default")
      (node (ref "U22") (pin "U25") (pinfunction "DISP0_DAT14_U25") (pintype "passive"))
    )
    (net (code "176") (name "/UBSPI_CLK") (class "Default")
      (node (ref "U22") (pin "C25") (pinfunction "EIM_D16_C25") (pintype "passive"))
    )
    (net (code "177") (name "/UBSPI_CS") (class "Default")
      (node (ref "U22") (pin "G21") (pinfunction "EIM_D19_G21") (pintype "passive"))
    )
    (net (code "178") (name "/UBSPI_DI") (class "Default")
      (node (ref "U22") (pin "F21") (pinfunction "EIM_D17_F21") (pintype "passive"))
    )
    (net (code "179") (name "/UBSPI_DO") (class "Default")
      (node (ref "U22") (pin "D24") (pinfunction "EIM_D18_D24") (pintype "passive"))
    )
    (net (code "180") (name "/UBSPI_WP") (class "Default")
      (node (ref "U22") (pin "G20") (pinfunction "EIM_D20_G20") (pintype "passive"))
    )
    (net (code "181") (name "/UHS_DN") (class "Default")
      (node (ref "R177") (pin "2") (pinfunction "2_2") (pintype "passive"))
      (node (ref "U22") (pin "F10") (pinfunction "USB_H1_DN_F10") (pintype "passive"))
    )
    (net (code "182") (name "/UHS_DP") (class "Default")
      (node (ref "R179") (pin "2") (pinfunction "2_2") (pintype "passive"))
      (node (ref "U22") (pin "E10") (pinfunction "USB_H1_DP_E10") (pintype "passive"))
    )
    (net (code "183") (name "/UHS_VBUS") (class "Default")
      (node (ref "C27") (pin "1") (pinfunction "1_1") (pintype "passive"))
      (node (ref "R397") (pin "2") (pinfunction "2_2") (pintype "passive"))
      (node (ref "U22") (pin "D10") (pinfunction "USB_H1_VBUS_D10") (pintype "passive"))
    )
    (net (code "184") (name "/UOTG_DN") (class "Default")
      (node (ref "U22") (pin "B6") (pinfunction "USB_OTG_DN_B6") (pintype "passive"))
    )
    (net (code "185") (name "/UOTG_DP") (class "Default")
      (node (ref "U22") (pin "A6") (pinfunction "USB_OTG_DP_A6") (pintype "passive"))
    )
    (net (code "186") (name "/UOTG_VBUS") (class "Default")
      (node (ref "R556") (pin "2") (pinfunction "2_2") (pintype "passive"))
      (node (ref "U22") (pin "E9") (pinfunction "USB_OTG_VBUS_E9") (pintype "passive"))
    )
    (net (code "187") (name "/UOYG_CHD_B") (class "Default")
      (node (ref "R395") (pin "2") (pinfunction "2_2") (pintype "passive"))
      (node (ref "U22") (pin "B8") (pinfunction "USB_OTG_CHD_B_B8") (pintype "passive"))
    )
    (net (code "188") (name "/USB_DEC") (class "Default")
      (node (ref "C135") (pin "1") (pinfunction "1_1") (pintype "passive"))
      (node (ref "R428") (pin "1") (pinfunction "1_1") (pintype "passive"))
      (node (ref "U22") (pin "T23") (pinfunction "DISP0_DAT11_T23") (pintype "passive"))
    )
    (net (code "189") (name "/USB_SW") (class "Default")
      (node (ref "U22") (pin "B15") (pinfunction "SD3_DATA3_B15") (pintype "passive"))
    )
    (net (code "190") (name "/WAN_WK") (class "Default")
      (node (ref "U22") (pin "J20") (pinfunction "EIM_D30_J20") (pintype "passive"))
    )
    (net (code "191") (name "/WB_RST") (class "Default")
      (node (ref "U22") (pin "P5") (pinfunction "GPIO_19_P5") (pintype "passive"))
    )
    (net (code "192") (name "/WDOG") (class "Default")
      (node (ref "U22") (pin "T2") (pinfunction "GPIO_9_T2") (pintype "passive"))
    )
    (net (code "193") (name "/WLBT_WK") (class "Default")
      (node (ref "U22") (pin "H21") (pinfunction "EIM_D31_H21") (pintype "passive"))
    )
    (net (code "194") (name "/{slash}ALS_INT") (class "Default")
      (node (ref "R125") (pin "2") (pinfunction "2_2") (pintype "passive"))
      (node (ref "U12") (pin "4") (pinfunction "/INT_4") (pintype "passive"))
      (node (ref "U22") (pin "T4") (pinfunction "GPIO_1_T4") (pintype "passive"))
      (node (ref "U30") (pin "7") (pinfunction "~{INT}_7") (pintype "passive"))
    )
    (net (code "195") (name "/{slash}AUD_SD") (class "Default")
      (node (ref "U22") (pin "F16") (pinfunction "NANDF_D2_F16") (pintype "passive"))
    )
    (net (code "196") (name "/{slash}CAM_SD") (class "Default")
      (node (ref "U22") (pin "W20") (pinfunction "ENET_TXD1_W20") (pintype "passive"))
    )
    (net (code "197") (name "/{slash}CARD_SD") (class "Default")
      (node (ref "U22") (pin "V23") (pinfunction "ENET_MDIO_V23") (pintype "passive"))
    )
    (net (code "198") (name "/{slash}CHAG") (class "Default")
      (node (ref "U22") (pin "E15") (pinfunction "NANDF_WP_B_E15") (pintype "passive"))
    )
    (net (code "199") (name "/{slash}EPHO_IN") (class "Default")
      (node (ref "U22") (pin "E14") (pinfunction "SD3_DATA0_E14") (pintype "passive"))
    )
    (net (code "200") (name "/{slash}SIM_SD") (class "Default")
      (node (ref "U22") (pin "C15") (pinfunction "NANDF_CLE_C15") (pintype "passive"))
    )
    (net (code "201") (name "/{slash}TP_SD") (class "Default")
      (node (ref "U22") (pin "A19") (pinfunction "NANDF_D4_A19") (pintype "passive"))
    )
    (net (code "202") (name "/{slash}VHS_SD") (class "Default")
      (node (ref "U22") (pin "D16") (pinfunction "NANDF_CS3_D16") (pintype "passive"))
    )
    (net (code "203") (name "/{slash}WB_PDN") (class "Default")
      (node (ref "U22") (pin "P6") (pinfunction "GPIO_18_P6") (pintype "passive"))
    )
    (net (code "204") (name "/{slash}WB_SD") (class "Default")
      (node (ref "U22") (pin "C17") (pinfunction "NANDF_D1_C17") (pintype "passive"))
    )
    (net (code "205") (name "GND") (class "Default")
      (node (ref "C13") (pin "2") (pinfunction "2_2") (pintype "passive"))
      (node (ref "C135") (pin "2") (pinfunction "2_2") (pintype "passive"))
      (node (ref "C213") (pin "2") (pinfunction "2_2") (pintype "passive"))
      (node (ref "C214") (pin "2") (pinfunction "2_2") (pintype "passive"))
      (node (ref "C258") (pin "1") (pinfunction "1_1") (pintype "passive"))
      (node (ref "C264") (pin "1") (pinfunction "1_1") (pintype "passive"))
      (node (ref "C267") (pin "1") (pinfunction "1_1") (pintype "passive"))
      (node (ref "C27") (pin "2") (pinfunction "2_2") (pintype "passive"))
      (node (ref "C320") (pin "1") (pinfunction "1_1") (pintype "passive"))
      (node (ref "C329") (pin "1") (pinfunction "1_1") (pintype "passive"))
      (node (ref "C40") (pin "2") (pinfunction "2_2") (pintype "passive"))
      (node (ref "C41") (pin "2") (pinfunction "2_2") (pintype "passive"))
      (node (ref "C42") (pin "2") (pinfunction "2_2") (pintype "passive"))
      (node (ref "C45") (pin "2") (pinfunction "2_2") (pintype "passive"))
      (node (ref "C46") (pin "2") (pinfunction "2_2") (pintype "passive"))
      (node (ref "C50") (pin "1") (pinfunction "1_1") (pintype "passive"))
      (node (ref "C53") (pin "2") (pinfunction "2_2") (pintype "passive"))
      (node (ref "C55") (pin "1") (pinfunction "1_1") (pintype "passive"))
      (node (ref "C56") (pin "1") (pinfunction "1_1") (pintype "passive"))
      (node (ref "C57") (pin "1") (pinfunction "1_1") (pintype "passive"))
      (node (ref "C8") (pin "1") (pinfunction "1_1") (pintype "passive"))
      (node (ref "J16") (pin "6") (pinfunction "6_6") (pintype "passive"))
      (node (ref "J16") (pin "7") (pinfunction "7_7") (pintype "passive"))
      (node (ref "J16") (pin "8") (pinfunction "8_8") (pintype "passive"))
      (node (ref "J2") (pin "15") (pinfunction "DGND_15") (pintype "passive"))
      (node (ref "J2") (pin "2") (pinfunction "AGND_2") (pintype "passive"))
      (node (ref "J2") (pin "25") (pinfunction "GND_25") (pintype "passive"))
      (node (ref "J2") (pin "26") (pinfunction "GND_26") (pintype "passive"))
      (node (ref "J3") (pin "1") (pinfunction "GND_1") (pintype "passive"))
      (node (ref "J3") (pin "10") (pinfunction "GND_10") (pintype "passive"))
      (node (ref "J3") (pin "12") (pinfunction "GND_12") (pintype "passive"))
      (node (ref "J3") (pin "14") (pinfunction "GND_14") (pintype "passive"))
      (node (ref "J3") (pin "15") (pinfunction "GND_15") (pintype "passive"))
      (node (ref "J3") (pin "18") (pinfunction "GND_18") (pintype "passive"))
      (node (ref "J3") (pin "20") (pinfunction "GND_20") (pintype "passive"))
      (node (ref "J3") (pin "23") (pinfunction "GND_23") (pintype "passive"))
      (node (ref "J3") (pin "26") (pinfunction "GND_26") (pintype "passive"))
      (node (ref "J3") (pin "3") (pinfunction "GND_3") (pintype "passive"))
      (node (ref "J3") (pin "7") (pinfunction "GND_7") (pintype "passive"))
      (node (ref "J3") (pin "9") (pinfunction "GND_9") (pintype "passive"))
      (node (ref "J6") (pin "10") (pinfunction "TMDS_DATA0_SHIELD_10") (pintype "passive"))
      (node (ref "J6") (pin "13") (pinfunction "TMDS_CLOCK_SHIELD_13") (pintype "passive"))
      (node (ref "J6") (pin "16") (pinfunction "DDC/CEC_GND_16") (pintype "passive"))
      (node (ref "J6") (pin "20") (pinfunction "SH1_20") (pintype "passive"))
      (node (ref "J6") (pin "21") (pinfunction "SH2_21") (pintype "passive"))
      (node (ref "J6") (pin "22") (pinfunction "SH3_22") (pintype "passive"))
      (node (ref "J6") (pin "23") (pinfunction "SH4_23") (pintype "passive"))
      (node (ref "J6") (pin "4") (pinfunction "TMDS_DATA2_SHIELD_4") (pintype "passive"))
      (node (ref "J6") (pin "7") (pinfunction "TMDS_DATA1_SHIELD_7") (pintype "passive"))
      (node (ref "J8") (pin "1") (pintype "passive"))
      (node (ref "Q10") (pin "3") (pinfunction "D_3") (pintype "passive"))
      (node (ref "R107") (pin "1") (pinfunction "1_1") (pintype "passive"))
      (node (ref "R110") (pin "2") (pinfunction "2_2") (pintype "passive"))
      (node (ref "R136") (pin "1") (pinfunction "1_1") (pintype "passive"))
      (node (ref "R137") (pin "1") (pinfunction "1_1") (pintype "passive"))
      (node (ref "R177") (pin "1") (pinfunction "1_1") (pintype "passive"))
      (node (ref "R179") (pin "1") (pinfunction "1_1") (pintype "passive"))
      (node (ref "R273") (pin "2") (pinfunction "2_2") (pintype "passive"))
      (node (ref "R274") (pin "2") (pinfunction "2_2") (pintype "passive"))
      (node (ref "R275") (pin "2") (pinfunction "2_2") (pintype "passive"))
      (node (ref "R276") (pin "2") (pinfunction "2_2") (pintype "passive"))
      (node (ref "R279") (pin "2") (pinfunction "2_2") (pintype "passive"))
      (node (ref "R323") (pin "1") (pinfunction "1_1") (pintype "passive"))
      (node (ref "R333") (pin "1") (pinfunction "1_1") (pintype "passive"))
      (node (ref "R395") (pin "1") (pinfunction "1_1") (pintype "passive"))
      (node (ref "R397") (pin "1") (pinfunction "1_1") (pintype "passive"))
      (node (ref "R491") (pin "2") (pinfunction "2_2") (pintype "passive"))
      (node (ref "R495") (pin "2") (pinfunction "2_2") (pintype "passive"))
      (node (ref "R75") (pin "2") (pinfunction "2_2") (pintype "passive"))
      (node (ref "R78") (pin "2") (pinfunction "2_2") (pintype "passive"))
      (node (ref "R79") (pin "2") (pinfunction "2_2") (pintype "passive"))
      (node (ref "R80") (pin "2") (pinfunction "2_2") (pintype "passive"))
      (node (ref "R90") (pin "2") (pinfunction "2_2") (pintype "passive"))
      (node (ref "U1") (pin "10") (pinfunction "GND_10") (pintype "passive"))
      (node (ref "U1") (pin "12") (pinfunction "GND_12") (pintype "passive"))
      (node (ref "U1") (pin "13") (pinfunction "NC_13") (pintype "passive"))
      (node (ref "U1") (pin "15") (pinfunction "NC_15") (pintype "passive"))
      (node (ref "U1") (pin "16") (pinfunction "NC_16") (pintype "passive"))
      (node (ref "U1") (pin "5") (pinfunction "GND_5") (pintype "passive"))
      (node (ref "U1") (pin "8") (pinfunction "NC_8") (pintype "passive"))
      (node (ref "U12") (pin "2") (pinfunction "GND_2") (pintype "passive"))
      (node (ref "U12") (pin "7") (pinfunction "PAD_7") (pintype "passive"))
      (node (ref "U27") (pin "2") (pinfunction "GND_2") (pintype "passive"))
      (node (ref "U30") (pin "1") (pinfunction "ADDR0_1") (pintype "passive"))
      (node (ref "U30") (pin "3") (pinfunction "GND_3") (pintype "passive"))
      (node (ref "U9") (pin "10") (pinfunction "RES_10") (pintype "passive"))
      (node (ref "U9") (pin "11") (pinfunction "RES_11") (pintype "passive"))
      (node (ref "U9") (pin "12") (pinfunction "RES_12") (pintype "passive"))
      (node (ref "U9") (pin "13") (pinfunction "GND_13") (pintype "passive"))
      (node (ref "U9") (pin "8") (pinfunction "RES_8") (pintype "passive"))
      (node (ref "U9") (pin "9") (pinfunction "RES_9") (pintype "passive"))
    )
    (net (code "206") (name "Net-(C58-Pad1)") (class "Default")
      (node (ref "C58") (pin "1") (pinfunction "1_1") (pintype "passive"))
      (node (ref "R75") (pin "1") (pinfunction "1_1") (pintype "passive"))
    )
    (net (code "207") (name "Net-(D4-Pad1)") (class "Default")
      (node (ref "D4") (pin "1") (pinfunction "1_1") (pintype "passive"))
      (node (ref "R332") (pin "1") (pinfunction "1_1") (pintype "passive"))
    )
    (net (code "208") (name "Net-(J2-XCLK)") (class "Default")
      (node (ref "J2") (pin "13") (pinfunction "XCLK_13") (pintype "passive"))
      (node (ref "R112") (pin "2") (pinfunction "2_2") (pintype "passive"))
    )
    (net (code "209") (name "Net-(J3-MCLK)") (class "Default")
      (node (ref "J3") (pin "19") (pinfunction "MCLK_19") (pintype "passive"))
      (node (ref "R127") (pin "1") (pinfunction "1_1") (pintype "passive"))
    )
    (net (code "210") (name "Net-(R315-Pad1)") (class "Default")
      (node (ref "R315") (pin "1") (pinfunction "1_1") (pintype "passive"))
      (node (ref "R323") (pin "2") (pinfunction "2_2") (pintype "passive"))
      (node (ref "R428") (pin "2") (pinfunction "2_2") (pintype "passive"))
    )
    (net (code "211") (name "Net-(T13-TP)") (class "Default")
      (node (ref "J16") (pin "3") (pinfunction "3_3") (pintype "passive"))
      (node (ref "R156") (pin "2") (pinfunction "2_2") (pintype "passive"))
      (node (ref "T13") (pin "1") (pinfunction "TP_1") (pintype "passive"))
    )
    (net (code "212") (name "Net-(T14-TP)") (class "Default")
      (node (ref "J16") (pin "2") (pinfunction "2_2") (pintype "passive"))
      (node (ref "R150") (pin "2") (pinfunction "2_2") (pintype "passive"))
      (node (ref "T14") (pin "1") (pinfunction "TP_1") (pintype "passive"))
    )
    (net (code "213") (name "Net-(T17-TP)") (class "Default")
      (node (ref "J16") (pin "5") (pinfunction "5_5") (pintype "passive"))
      (node (ref "R164") (pin "2") (pinfunction "2_2") (pintype "passive"))
      (node (ref "T17") (pin "1") (pinfunction "TP_1") (pintype "passive"))
    )
    (net (code "214") (name "Net-(T18-TP)") (class "Default")
      (node (ref "J16") (pin "4") (pinfunction "4_4") (pintype "passive"))
      (node (ref "R159") (pin "2") (pinfunction "2_2") (pintype "passive"))
      (node (ref "T18") (pin "1") (pinfunction "TP_1") (pintype "passive"))
    )
    (net (code "215") (name "Net-(U1-BYP)") (class "Default")
      (node (ref "C8") (pin "2") (pinfunction "2_2") (pintype "passive"))
      (node (ref "U1") (pin "2") (pinfunction "BYP_2") (pintype "passive"))
    )
    (net (code "216") (name "Net-(U1-SA0)") (class "Default")
      (node (ref "R107") (pin "2") (pinfunction "2_2") (pintype "passive"))
      (node (ref "U1") (pin "7") (pinfunction "SA0_7") (pintype "passive"))
    )
    (net (code "217") (name "Net-(U9-PLLFILT)") (class "Default")
      (node (ref "C57") (pin "2") (pinfunction "2_2") (pintype "passive"))
      (node (ref "C58") (pin "2") (pinfunction "2_2") (pintype "passive"))
      (node (ref "U9") (pin "14") (pinfunction "PLLFILT_14") (pintype "passive"))
    )
    (net (code "218") (name "Net-(U12-REXT)") (class "Default")
      (node (ref "R136") (pin "2") (pinfunction "2_2") (pintype "passive"))
      (node (ref "U12") (pin "3") (pinfunction "REXT_3") (pintype "passive"))
    )
    (net (code "219") (name "Net-(U12-SCL)") (class "Default")
      (node (ref "R69") (pin "2") (pinfunction "2_2") (pintype "passive"))
      (node (ref "U12") (pin "5") (pinfunction "SCL_5") (pintype "passive"))
    )
    (net (code "220") (name "Net-(U12-SDA)") (class "Default")
      (node (ref "R70") (pin "2") (pinfunction "2_2") (pintype "passive"))
      (node (ref "U12") (pin "6") (pinfunction "SDA_6") (pintype "passive"))
    )
    (net (code "221") (name "Net-(U22B-CSI_REXT)") (class "Default")
      (node (ref "R279") (pin "1") (pinfunction "1_1") (pintype "passive"))
      (node (ref "U22") (pin "D4") (pinfunction "CSI_REXT_D4") (pintype "passive"))
    )
    (net (code "222") (name "Net-(U22B-DSI_REXT)") (class "Default")
      (node (ref "R137") (pin "2") (pinfunction "2_2") (pintype "passive"))
      (node (ref "U22") (pin "G4") (pinfunction "DSI_REXT_G4") (pintype "passive"))
    )
    (net (code "223") (name "Net-(U22B-HDMI_REF)") (class "Default")
      (node (ref "R110") (pin "1") (pinfunction "1_1") (pintype "passive"))
      (node (ref "U22") (pin "J1") (pinfunction "HDMI_REF_J1") (pintype "passive"))
    )
    (net (code "224") (name "Net-(U30-IRDR)") (class "Default")
      (node (ref "D4") (pin "2") (pinfunction "2_2") (pintype "passive"))
      (node (ref "U30") (pin "8") (pinfunction "IRDR_8") (pintype "passive"))
    )
    (net (code "225") (name "Net-(U30-REXT)") (class "Default")
      (node (ref "R333") (pin "2") (pinfunction "2_2") (pintype "passive"))
      (node (ref "U30") (pin "4") (pinfunction "REXT_4") (pintype "passive"))
    )
    (net (code "226") (name "USB_BUSIN") (class "Default")
      (node (ref "R315") (pin "2") (pinfunction "2_2") (pintype "passive"))
      (node (ref "R556") (pin "1") (pinfunction "1_1") (pintype "passive"))
      (node (ref "R566") (pin "1") (pinfunction "1_1") (pintype "passive"))
    )
    (net (code "227") (name "VBUS") (class "Default")
      (node (ref "R566") (pin "2") (pinfunction "2_2") (pintype "passive"))
      (node (ref "R74") (pin "1") (pinfunction "1_1") (pintype "passive"))
    )
    (net (code "228") (name "VCC_3V") (class "Default")
      (node (ref "C13") (pin "1") (pinfunction "1_1") (pintype "passive"))
      (node (ref "R121") (pin "1") (pinfunction "1_1") (pintype "passive"))
      (node (ref "R122") (pin "1") (pinfunction "1_1") (pintype "passive"))
      (node (ref "U27") (pin "1") (pinfunction "VCCA_1") (pintype "passive"))
    )
    (net (code "229") (name "VCC_ACC") (class "Default")
      (node (ref "C320") (pin "2") (pinfunction "2_2") (pintype "passive"))
      (node (ref "C329") (pin "2") (pinfunction "2_2") (pintype "passive"))
      (node (ref "R372") (pin "1") (pinfunction "1_1") (pintype "passive"))
      (node (ref "R373") (pin "1") (pinfunction "1_1") (pintype "passive"))
      (node (ref "R56") (pin "2") (pinfunction "2_2") (pintype "passive"))
      (node (ref "U1") (pin "1") (pinfunction "VDDIO_1") (pintype "passive"))
      (node (ref "U1") (pin "14") (pinfunction "VDD_14") (pintype "passive"))
    )
    (net (code "230") (name "VCC_ALS") (class "Default")
      (node (ref "C264") (pin "2") (pinfunction "2_2") (pintype "passive"))
      (node (ref "C267") (pin "2") (pinfunction "2_2") (pintype "passive"))
      (node (ref "C41") (pin "1") (pinfunction "1_1") (pintype "passive"))
      (node (ref "C42") (pin "1") (pinfunction "1_1") (pintype "passive"))
      (node (ref "Q10") (pin "1") (pinfunction "G_1") (pintype "passive"))
      (node (ref "R125") (pin "1") (pinfunction "1_1") (pintype "passive"))
      (node (ref "R331") (pin "2") (pinfunction "2_2") (pintype "passive"))
      (node (ref "R332") (pin "2") (pinfunction "2_2") (pintype "passive"))
      (node (ref "R72") (pin "2") (pinfunction "2_2") (pintype "passive"))
      (node (ref "R94") (pin "2") (pinfunction "2_2") (pintype "passive"))
      (node (ref "R95") (pin "2") (pinfunction "2_2") (pintype "passive"))
      (node (ref "U12") (pin "1") (pinfunction "VDD_1") (pintype "passive"))
      (node (ref "U30") (pin "2") (pinfunction "VDD_2") (pintype "passive"))
    )
    (net (code "231") (name "VCC_CAM") (class "Default")
      (node (ref "C45") (pin "1") (pinfunction "1_1") (pintype "passive"))
      (node (ref "C46") (pin "1") (pinfunction "1_1") (pintype "passive"))
      (node (ref "C56") (pin "2") (pinfunction "2_2") (pintype "passive"))
      (node (ref "J2") (pin "11") (pinfunction "DOVDD_11") (pintype "passive"))
      (node (ref "J2") (pin "4") (pinfunction "AVDD_4") (pintype "passive"))
      (node (ref "J3") (pin "11") (pinfunction "AF_2.8V_11") (pintype "passive"))
      (node (ref "J3") (pin "6") (pinfunction "VDDIO_1.8V_6") (pintype "passive"))
      (node (ref "J3") (pin "8") (pinfunction "AVDD_2.8V_8") (pintype "passive"))
      (node (ref "R101") (pin "1") (pinfunction "1_1") (pintype "passive"))
      (node (ref "R98") (pin "1") (pinfunction "1_1") (pintype "passive"))
    )
    (net (code "232") (name "VCC_CAMD") (class "Default")
      (node (ref "C258") (pin "2") (pinfunction "2_2") (pintype "passive"))
      (node (ref "C53") (pin "1") (pinfunction "1_1") (pintype "passive"))
      (node (ref "J2") (pin "10") (pinfunction "DVDD_10") (pintype "passive"))
      (node (ref "J3") (pin "4") (pinfunction "DVDD_1.2V_4") (pintype "passive"))
      (node (ref "J3") (pin "5") (pinfunction "DVDD_1.2V_5") (pintype "passive"))
    )
    (net (code "233") (name "VCC_CSI") (class "Default")
      (node (ref "R399") (pin "1") (pinfunction "1_1") (pintype "passive"))
    )
    (net (code "234") (name "VCC_GYR") (class "Default")
      (node (ref "C50") (pin "2") (pinfunction "2_2") (pintype "passive"))
      (node (ref "C55") (pin "2") (pinfunction "2_2") (pintype "passive"))
      (node (ref "R103") (pin "2") (pinfunction "2_2") (pintype "passive"))
      (node (ref "R104") (pin "2") (pinfunction "2_2") (pintype "passive"))
      (node (ref "R73") (pin "2") (pinfunction "2_2") (pintype "passive"))
      (node (ref "U9") (pin "1") (pinfunction "VDDIO_1") (pintype "passive"))
      (node (ref "U9") (pin "15") (pinfunction "RES_15") (pintype "passive"))
      (node (ref "U9") (pin "16") (pinfunction "VDD_16") (pintype "passive"))
    )
    (net (code "235") (name "VCC_HD") (class "Default")
      (node (ref "J6") (pin "19") (pinfunction "+5V_19") (pintype "passive"))
      (node (ref "R105") (pin "2") (pinfunction "2_2") (pintype "passive"))
      (node (ref "R106") (pin "2") (pinfunction "2_2") (pintype "passive"))
      (node (ref "R492") (pin "2") (pinfunction "2_2") (pintype "passive"))
      (node (ref "R74") (pin "2") (pinfunction "2_2") (pintype "passive"))
    )
    (net (code "236") (name "VCC_MCLK") (class "Default")
      (node (ref "C40") (pin "1") (pinfunction "1_1") (pintype "passive"))
      (node (ref "R399") (pin "2") (pinfunction "2_2") (pintype "passive"))
      (node (ref "R400") (pin "2") (pinfunction "2_2") (pintype "passive"))
      (node (ref "U27") (pin "5") (pinfunction "DIR_5") (pintype "passive"))
      (node (ref "U27") (pin "6") (pinfunction "VCCB_6") (pintype "passive"))
    )
    (net (code "237") (name "VCC_MEMS") (class "Default")
      (node (ref "R56") (pin "1") (pinfunction "1_1") (pintype "passive"))
      (node (ref "R72") (pin "1") (pinfunction "1_1") (pintype "passive"))
      (node (ref "R73") (pin "1") (pinfunction "1_1") (pintype "passive"))
    )
    (net (code "238") (name "VCC_MIPI") (class "Default")
      (node (ref "R400") (pin "1") (pinfunction "1_1") (pintype "passive"))
    )
    (net (code "239") (name "VCC_TOUCH") (class "Default")
      (node (ref "C213") (pin "1") (pinfunction "1_1") (pintype "passive"))
      (node (ref "C214") (pin "1") (pinfunction "1_1") (pintype "passive"))
      (node (ref "J16") (pin "1") (pinfunction "1_1") (pintype "passive"))
      (node (ref "R143") (pin "1") (pinfunction "1_1") (pintype "passive"))
      (node (ref "R24") (pin "1") (pinfunction "1_1") (pintype "passive"))
      (node (ref "R357") (pin "1") (pinfunction "1_1") (pintype "passive"))
      (node (ref "R77") (pin "1") (pinfunction "1_1") (pintype "passive"))
      (node (ref "T16") (pin "1") (pinfunction "TP_1") (pintype "passive"))
    )
    (net (code "240") (name "unconnected-(J3-NC-Pad2)") (class "Default")
      (node (ref "J3") (pin "2") (pinfunction "NC_2") (pintype "passive"))
    )
    (net (code "241") (name "unconnected-(J6-RESERVED-Pad2)") (class "Default")
      (node (ref "J6") (pin "2") (pinfunction "RESERVED_2") (pintype "passive"))
    )
    (net (code "242") (name "unconnected-(U1-NC-Pad3)") (class "Default")
      (node (ref "U1") (pin "3") (pinfunction "NC_3") (pintype "passive+no_connect"))
    )
  )
)
